# thinks.net
KiCad netlist of a schematic drawn in EAGLE
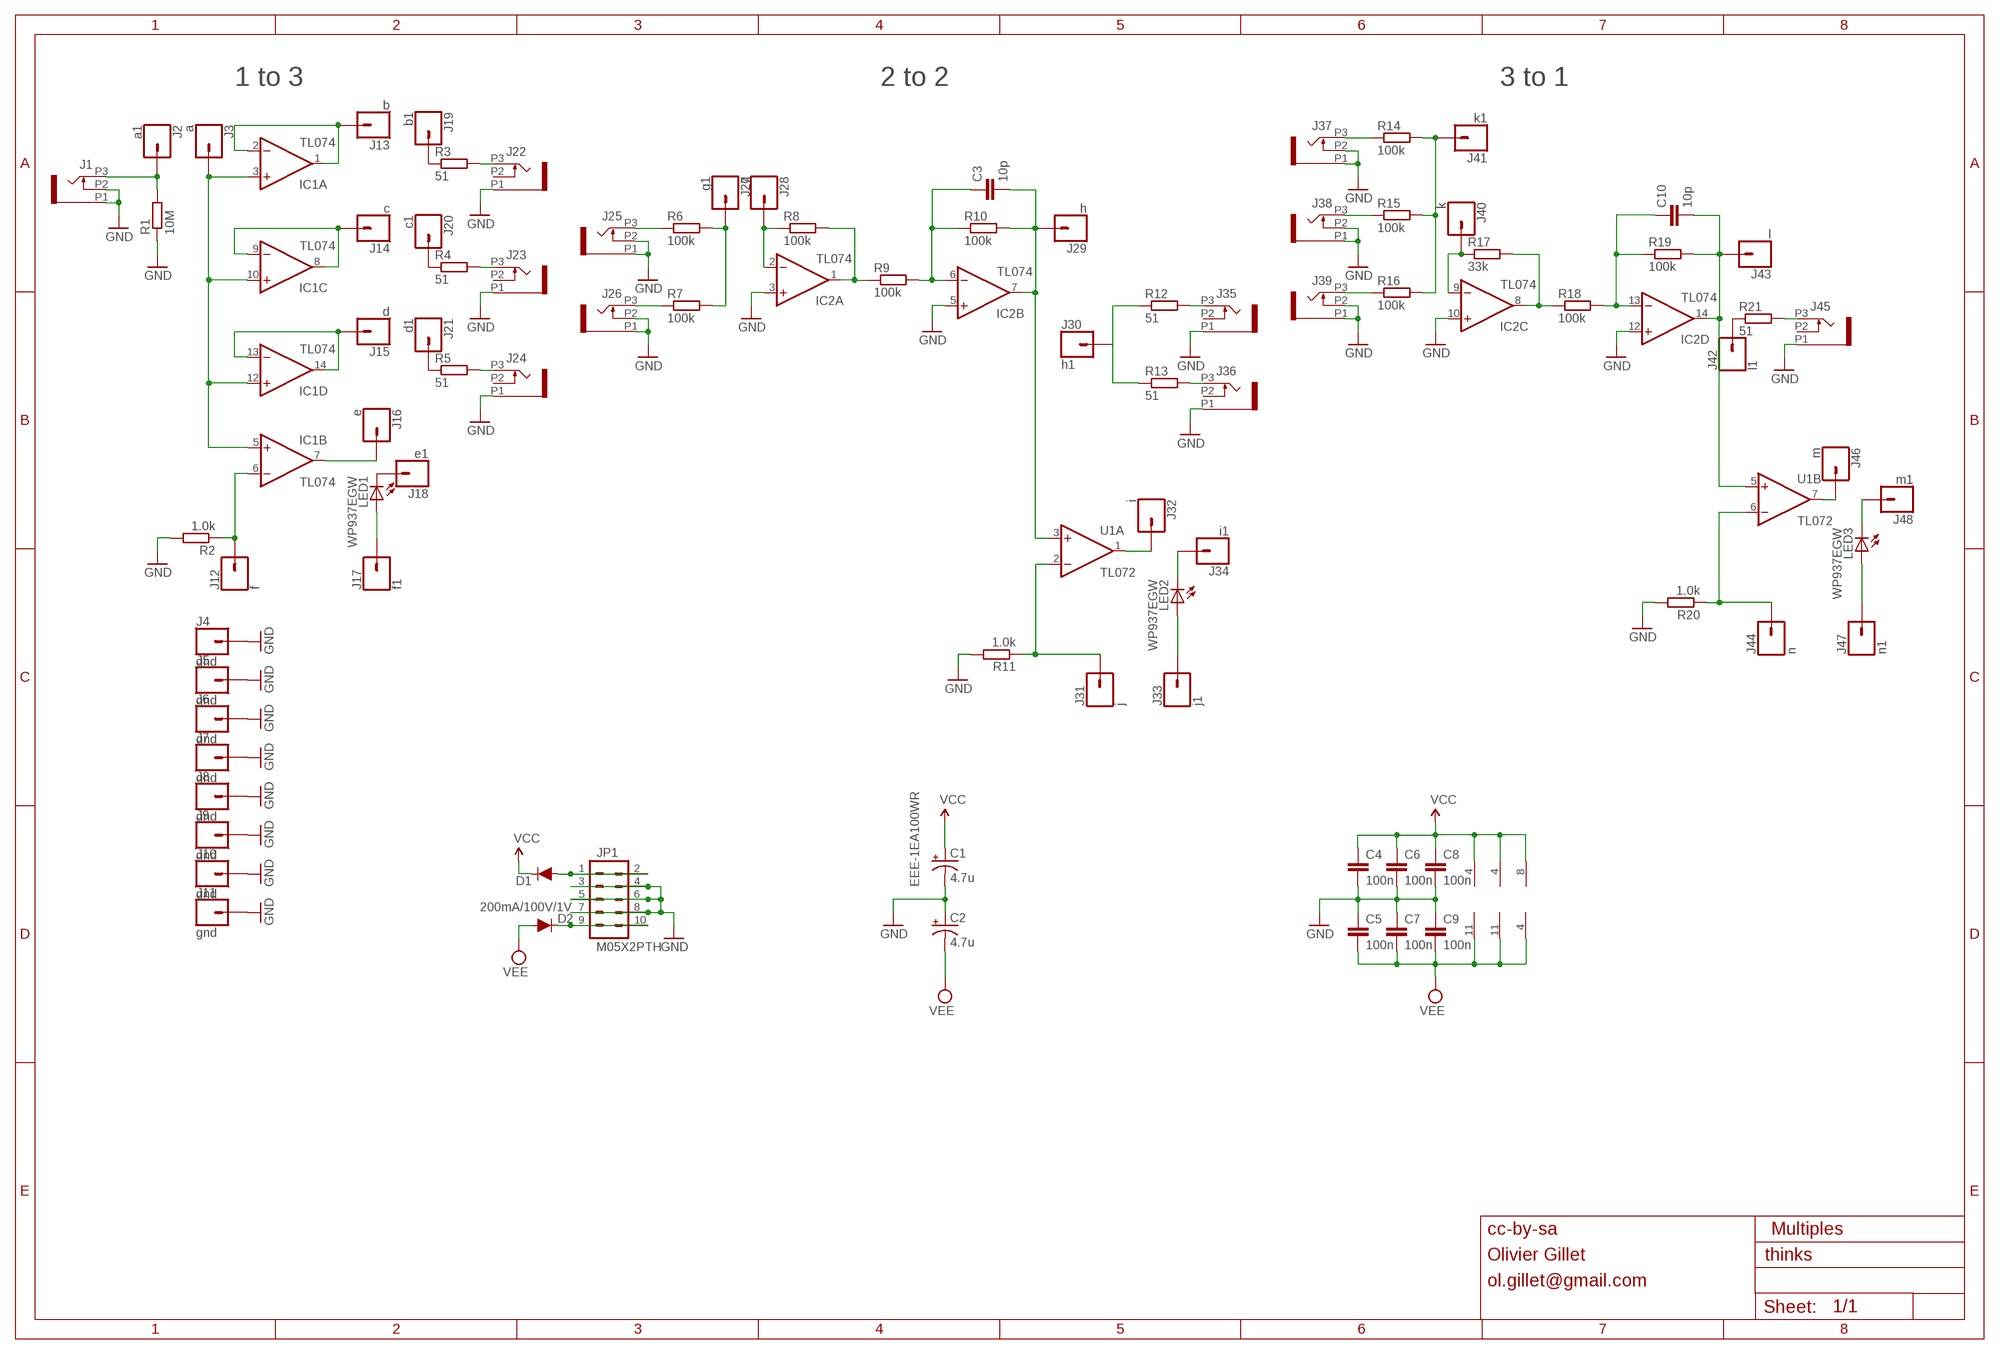
[diagram p0: schematic, sheet 1]

(export (version "E")
  (design (tool "Eeschema 10.0.6"))
  (components
    (comp (ref "C1")
      (value "4.7u")
      (footprint "eagle-import:E2,5-6")
      (libsource (lib "eagle-import") (part "CPOL-USE2.5-6"))
    )
    (comp (ref "C2")
      (value "4.7u")
      (footprint "eagle-import:E2,5-6")
      (libsource (lib "eagle-import") (part "CPOL-USE2.5-6"))
    )
    (comp (ref "C3")
      (value "10p")
      (footprint "eagle-import:C5B2.5")
      (libsource (lib "eagle-import") (part "C5/2.5"))
    )
    (comp (ref "C4")
      (value "100n")
      (footprint "eagle-import:C5B2.5")
      (libsource (lib "eagle-import") (part "C5/2.5"))
    )
    (comp (ref "C5")
      (value "100n")
      (footprint "eagle-import:C5B2.5")
      (libsource (lib "eagle-import") (part "C5/2.5"))
    )
    (comp (ref "C6")
      (value "100n")
      (footprint "eagle-import:C5B2.5")
      (libsource (lib "eagle-import") (part "C5/2.5"))
    )
    (comp (ref "C7")
      (value "100n")
      (footprint "eagle-import:C5B2.5")
      (libsource (lib "eagle-import") (part "C5/2.5"))
    )
    (comp (ref "C8")
      (value "100n")
      (footprint "eagle-import:C5B2.5")
      (libsource (lib "eagle-import") (part "C5/2.5"))
    )
    (comp (ref "C9")
      (value "100n")
      (footprint "eagle-import:C5B2.5")
      (libsource (lib "eagle-import") (part "C5/2.5"))
    )
    (comp (ref "C10")
      (value "10p")
      (footprint "eagle-import:C5B2.5")
      (libsource (lib "eagle-import") (part "C5/2.5"))
    )
    (comp (ref "D1")
      (value "200mA/100V/1V")
      (footprint "eagle-import:DIODE-1N4148")
      (libsource (lib "eagle-import") (part "DIODE-1N4148"))
    )
    (comp (ref "D2")
      (value "200mA/100V/1V")
      (footprint "eagle-import:DIODE-1N4148")
      (libsource (lib "eagle-import") (part "DIODE-1N4148"))
    )
    (comp (ref "IC1")
      (value "TL074")
      (footprint "eagle-import:DIL14")
      (libsource (lib "eagle-import") (part "TL074P"))
    )
    (comp (ref "IC2")
      (value "TL074")
      (footprint "eagle-import:DIL14")
      (libsource (lib "eagle-import") (part "TL074P"))
    )
    (comp (ref "J1")
      (value "PJ301_THONKICONN6")
      (footprint "eagle-import:WQP_PJ_301M6")
      (libsource (lib "eagle-import") (part "PJ301_THONKICONN6"))
    )
    (comp (ref "J2")
      (value "a1")
      (footprint "eagle-import:1X01")
      (libsource (lib "eagle-import") (part "CONN_01"))
    )
    (comp (ref "J3")
      (value "a")
      (footprint "eagle-import:1X01")
      (libsource (lib "eagle-import") (part "CONN_01"))
    )
    (comp (ref "J4")
      (value "gnd")
      (footprint "eagle-import:1X01")
      (libsource (lib "eagle-import") (part "CONN_01"))
    )
    (comp (ref "J5")
      (value "gnd")
      (footprint "eagle-import:1X01")
      (libsource (lib "eagle-import") (part "CONN_01"))
    )
    (comp (ref "J6")
      (value "gnd")
      (footprint "eagle-import:1X01")
      (libsource (lib "eagle-import") (part "CONN_01"))
    )
    (comp (ref "J7")
      (value "gnd")
      (footprint "eagle-import:1X01")
      (libsource (lib "eagle-import") (part "CONN_01"))
    )
    (comp (ref "J8")
      (value "gnd")
      (footprint "eagle-import:1X01")
      (libsource (lib "eagle-import") (part "CONN_01"))
    )
    (comp (ref "J9")
      (value "gnd")
      (footprint "eagle-import:1X01")
      (libsource (lib "eagle-import") (part "CONN_01"))
    )
    (comp (ref "J10")
      (value "gnd")
      (footprint "eagle-import:1X01")
      (libsource (lib "eagle-import") (part "CONN_01"))
    )
    (comp (ref "J11")
      (value "gnd")
      (footprint "eagle-import:1X01")
      (libsource (lib "eagle-import") (part "CONN_01"))
    )
    (comp (ref "J12")
      (value "f")
      (footprint "eagle-import:1X01")
      (libsource (lib "eagle-import") (part "CONN_01"))
    )
    (comp (ref "J13")
      (value "b")
      (footprint "eagle-import:1X01")
      (libsource (lib "eagle-import") (part "CONN_01"))
    )
    (comp (ref "J14")
      (value "c")
      (footprint "eagle-import:1X01")
      (libsource (lib "eagle-import") (part "CONN_01"))
    )
    (comp (ref "J15")
      (value "d")
      (footprint "eagle-import:1X01")
      (libsource (lib "eagle-import") (part "CONN_01"))
    )
    (comp (ref "J16")
      (value "e")
      (footprint "eagle-import:1X01")
      (libsource (lib "eagle-import") (part "CONN_01"))
    )
    (comp (ref "J17")
      (value "f1")
      (footprint "eagle-import:1X01")
      (libsource (lib "eagle-import") (part "CONN_01"))
    )
    (comp (ref "J18")
      (value "e1")
      (footprint "eagle-import:1X01")
      (libsource (lib "eagle-import") (part "CONN_01"))
    )
    (comp (ref "J19")
      (value "b1")
      (footprint "eagle-import:1X01")
      (libsource (lib "eagle-import") (part "CONN_01"))
    )
    (comp (ref "J20")
      (value "c1")
      (footprint "eagle-import:1X01")
      (libsource (lib "eagle-import") (part "CONN_01"))
    )
    (comp (ref "J21")
      (value "d1")
      (footprint "eagle-import:1X01")
      (libsource (lib "eagle-import") (part "CONN_01"))
    )
    (comp (ref "J22")
      (value "PJ301_THONKICONN6")
      (footprint "eagle-import:WQP_PJ_301M6")
      (libsource (lib "eagle-import") (part "PJ301_THONKICONN6"))
    )
    (comp (ref "J23")
      (value "PJ301_THONKICONN6")
      (footprint "eagle-import:WQP_PJ_301M6")
      (libsource (lib "eagle-import") (part "PJ301_THONKICONN6"))
    )
    (comp (ref "J24")
      (value "PJ301_THONKICONN6")
      (footprint "eagle-import:WQP_PJ_301M6")
      (libsource (lib "eagle-import") (part "PJ301_THONKICONN6"))
    )
    (comp (ref "J25")
      (value "PJ301_THONKICONN6")
      (footprint "eagle-import:WQP_PJ_301M6")
      (libsource (lib "eagle-import") (part "PJ301_THONKICONN6"))
    )
    (comp (ref "J26")
      (value "PJ301_THONKICONN6")
      (footprint "eagle-import:WQP_PJ_301M6")
      (libsource (lib "eagle-import") (part "PJ301_THONKICONN6"))
    )
    (comp (ref "J27")
      (value "g1")
      (footprint "eagle-import:1X01")
      (libsource (lib "eagle-import") (part "CONN_01"))
    )
    (comp (ref "J28")
      (value "g")
      (footprint "eagle-import:1X01")
      (libsource (lib "eagle-import") (part "CONN_01"))
    )
    (comp (ref "J29")
      (value "h")
      (footprint "eagle-import:1X01")
      (libsource (lib "eagle-import") (part "CONN_01"))
    )
    (comp (ref "J30")
      (value "h1")
      (footprint "eagle-import:1X01")
      (libsource (lib "eagle-import") (part "CONN_01"))
    )
    (comp (ref "J31")
      (value "j")
      (footprint "eagle-import:1X01")
      (libsource (lib "eagle-import") (part "CONN_01"))
    )
    (comp (ref "J32")
      (value "i")
      (footprint "eagle-import:1X01")
      (libsource (lib "eagle-import") (part "CONN_01"))
    )
    (comp (ref "J33")
      (value "j1")
      (footprint "eagle-import:1X01")
      (libsource (lib "eagle-import") (part "CONN_01"))
    )
    (comp (ref "J34")
      (value "i1")
      (footprint "eagle-import:1X01")
      (libsource (lib "eagle-import") (part "CONN_01"))
    )
    (comp (ref "J35")
      (value "PJ301_THONKICONN6")
      (footprint "eagle-import:WQP_PJ_301M6")
      (libsource (lib "eagle-import") (part "PJ301_THONKICONN6"))
    )
    (comp (ref "J36")
      (value "PJ301_THONKICONN6")
      (footprint "eagle-import:WQP_PJ_301M6")
      (libsource (lib "eagle-import") (part "PJ301_THONKICONN6"))
    )
    (comp (ref "J37")
      (value "PJ301_THONKICONN6")
      (footprint "eagle-import:WQP_PJ_301M6")
      (libsource (lib "eagle-import") (part "PJ301_THONKICONN6"))
    )
    (comp (ref "J38")
      (value "PJ301_THONKICONN6")
      (footprint "eagle-import:WQP_PJ_301M6")
      (libsource (lib "eagle-import") (part "PJ301_THONKICONN6"))
    )
    (comp (ref "J39")
      (value "PJ301_THONKICONN6")
      (footprint "eagle-import:WQP_PJ_301M6")
      (libsource (lib "eagle-import") (part "PJ301_THONKICONN6"))
    )
    (comp (ref "J40")
      (value "k")
      (footprint "eagle-import:1X01")
      (libsource (lib "eagle-import") (part "CONN_01"))
    )
    (comp (ref "J41")
      (value "k1")
      (footprint "eagle-import:1X01")
      (libsource (lib "eagle-import") (part "CONN_01"))
    )
    (comp (ref "J42")
      (value "l1")
      (footprint "eagle-import:1X01")
      (libsource (lib "eagle-import") (part "CONN_01"))
    )
    (comp (ref "J43")
      (value "l")
      (footprint "eagle-import:1X01")
      (libsource (lib "eagle-import") (part "CONN_01"))
    )
    (comp (ref "J44")
      (value "n")
      (footprint "eagle-import:1X01")
      (libsource (lib "eagle-import") (part "CONN_01"))
    )
    (comp (ref "J45")
      (value "PJ301_THONKICONN6")
      (footprint "eagle-import:WQP_PJ_301M6")
      (libsource (lib "eagle-import") (part "PJ301_THONKICONN6"))
    )
    (comp (ref "J46")
      (value "m")
      (footprint "eagle-import:1X01")
      (libsource (lib "eagle-import") (part "CONN_01"))
    )
    (comp (ref "J47")
      (value "n1")
      (footprint "eagle-import:1X01")
      (libsource (lib "eagle-import") (part "CONN_01"))
    )
    (comp (ref "J48")
      (value "m1")
      (footprint "eagle-import:1X01")
      (libsource (lib "eagle-import") (part "CONN_01"))
    )
    (comp (ref "JP1")
      (value "M05X2PTH")
      (footprint "eagle-import:AVR_ICSP")
      (libsource (lib "eagle-import") (part "M05X2PTH"))
    )
    (comp (ref "LED1")
      (value "WP937EGW")
      (footprint "eagle-import:LED3MM")
      (libsource (lib "eagle-import") (part "LED3MM"))
    )
    (comp (ref "LED2")
      (value "WP937EGW")
      (footprint "eagle-import:LED3MM")
      (libsource (lib "eagle-import") (part "LED3MM"))
    )
    (comp (ref "LED3")
      (value "WP937EGW")
      (footprint "eagle-import:LED3MM")
      (libsource (lib "eagle-import") (part "LED3MM"))
    )
    (comp (ref "R1")
      (value "10M")
      (footprint "eagle-import:VERTICAL_RESISTOR")
      (libsource (lib "eagle-import") (part "RESISTORVERTICAL"))
    )
    (comp (ref "R2")
      (value "1.0k")
      (footprint "eagle-import:VERTICAL_RESISTOR")
      (libsource (lib "eagle-import") (part "RESISTORVERTICAL"))
    )
    (comp (ref "R3")
      (value "51")
      (footprint "eagle-import:VERTICAL_RESISTOR")
      (libsource (lib "eagle-import") (part "RESISTORVERTICAL"))
    )
    (comp (ref "R4")
      (value "51")
      (footprint "eagle-import:VERTICAL_RESISTOR")
      (libsource (lib "eagle-import") (part "RESISTORVERTICAL"))
    )
    (comp (ref "R5")
      (value "51")
      (footprint "eagle-import:VERTICAL_RESISTOR")
      (libsource (lib "eagle-import") (part "RESISTORVERTICAL"))
    )
    (comp (ref "R6")
      (value "100k")
      (footprint "eagle-import:VERTICAL_RESISTOR")
      (libsource (lib "eagle-import") (part "RESISTORVERTICAL"))
    )
    (comp (ref "R7")
      (value "100k")
      (footprint "eagle-import:VERTICAL_RESISTOR")
      (libsource (lib "eagle-import") (part "RESISTORVERTICAL"))
    )
    (comp (ref "R8")
      (value "100k")
      (footprint "eagle-import:VERTICAL_RESISTOR")
      (libsource (lib "eagle-import") (part "RESISTORVERTICAL"))
    )
    (comp (ref "R9")
      (value "100k")
      (footprint "eagle-import:VERTICAL_RESISTOR")
      (libsource (lib "eagle-import") (part "RESISTORVERTICAL"))
    )
    (comp (ref "R10")
      (value "100k")
      (footprint "eagle-import:VERTICAL_RESISTOR")
      (libsource (lib "eagle-import") (part "RESISTORVERTICAL"))
    )
    (comp (ref "R11")
      (value "1.0k")
      (footprint "eagle-import:VERTICAL_RESISTOR")
      (libsource (lib "eagle-import") (part "RESISTORVERTICAL"))
    )
    (comp (ref "R12")
      (value "51")
      (footprint "eagle-import:VERTICAL_RESISTOR")
      (libsource (lib "eagle-import") (part "RESISTORVERTICAL"))
    )
    (comp (ref "R13")
      (value "51")
      (footprint "eagle-import:VERTICAL_RESISTOR")
      (libsource (lib "eagle-import") (part "RESISTORVERTICAL"))
    )
    (comp (ref "R14")
      (value "100k")
      (footprint "eagle-import:VERTICAL_RESISTOR")
      (libsource (lib "eagle-import") (part "RESISTORVERTICAL"))
    )
    (comp (ref "R15")
      (value "100k")
      (footprint "eagle-import:VERTICAL_RESISTOR")
      (libsource (lib "eagle-import") (part "RESISTORVERTICAL"))
    )
    (comp (ref "R16")
      (value "100k")
      (footprint "eagle-import:VERTICAL_RESISTOR")
      (libsource (lib "eagle-import") (part "RESISTORVERTICAL"))
    )
    (comp (ref "R17")
      (value "33k")
      (footprint "eagle-import:VERTICAL_RESISTOR")
      (libsource (lib "eagle-import") (part "RESISTORVERTICAL"))
    )
    (comp (ref "R18")
      (value "100k")
      (footprint "eagle-import:VERTICAL_RESISTOR")
      (libsource (lib "eagle-import") (part "RESISTORVERTICAL"))
    )
    (comp (ref "R19")
      (value "100k")
      (footprint "eagle-import:VERTICAL_RESISTOR")
      (libsource (lib "eagle-import") (part "RESISTORVERTICAL"))
    )
    (comp (ref "R20")
      (value "1.0k")
      (footprint "eagle-import:VERTICAL_RESISTOR")
      (libsource (lib "eagle-import") (part "RESISTORVERTICAL"))
    )
    (comp (ref "R21")
      (value "51")
      (footprint "eagle-import:VERTICAL_RESISTOR")
      (libsource (lib "eagle-import") (part "RESISTORVERTICAL"))
    )
    (comp (ref "U1")
      (value "TL072")
      (footprint "eagle-import:DIL08")
      (libsource (lib "eagle-import") (part "OP_DUAL_"))
    )
  )
  (nets
    (net (code "1") (name "GND") (class "Default")
      (node (ref "C1") (pin "-") (pinfunction "-_-") (pintype "passive"))
      (node (ref "C2") (pin "+") (pinfunction "+_+") (pintype "passive"))
      (node (ref "C4") (pin "2") (pinfunction "2_2") (pintype "passive"))
      (node (ref "C5") (pin "1") (pinfunction "1_1") (pintype "passive"))
      (node (ref "C6") (pin "2") (pinfunction "2_2") (pintype "passive"))
      (node (ref "C7") (pin "1") (pinfunction "1_1") (pintype "passive"))
      (node (ref "C8") (pin "2") (pinfunction "2_2") (pintype "passive"))
      (node (ref "C9") (pin "1") (pinfunction "1_1") (pintype "passive"))
      (node (ref "IC2") (pin "10") (pinfunction "+IN_10") (pintype "input"))
      (node (ref "IC2") (pin "12") (pinfunction "+IN_12") (pintype "input"))
      (node (ref "IC2") (pin "3") (pinfunction "+IN_3") (pintype "input"))
      (node (ref "IC2") (pin "5") (pinfunction "+IN_5") (pintype "input"))
      (node (ref "J1") (pin "P1") (pinfunction "1_P1") (pintype "passive"))
      (node (ref "J1") (pin "P2") (pinfunction "2_P2") (pintype "passive"))
      (node (ref "J10") (pin "1") (pinfunction "1_1") (pintype "passive"))
      (node (ref "J11") (pin "1") (pinfunction "1_1") (pintype "passive"))
      (node (ref "J22") (pin "P1") (pinfunction "1_P1") (pintype "passive"))
      (node (ref "J23") (pin "P1") (pinfunction "1_P1") (pintype "passive"))
      (node (ref "J24") (pin "P1") (pinfunction "1_P1") (pintype "passive"))
      (node (ref "J25") (pin "P1") (pinfunction "1_P1") (pintype "passive"))
      (node (ref "J25") (pin "P2") (pinfunction "2_P2") (pintype "passive"))
      (node (ref "J26") (pin "P1") (pinfunction "1_P1") (pintype "passive"))
      (node (ref "J26") (pin "P2") (pinfunction "2_P2") (pintype "passive"))
      (node (ref "J35") (pin "P1") (pinfunction "1_P1") (pintype "passive"))
      (node (ref "J36") (pin "P1") (pinfunction "1_P1") (pintype "passive"))
      (node (ref "J37") (pin "P1") (pinfunction "1_P1") (pintype "passive"))
      (node (ref "J37") (pin "P2") (pinfunction "2_P2") (pintype "passive"))
      (node (ref "J38") (pin "P1") (pinfunction "1_P1") (pintype "passive"))
      (node (ref "J38") (pin "P2") (pinfunction "2_P2") (pintype "passive"))
      (node (ref "J39") (pin "P1") (pinfunction "1_P1") (pintype "passive"))
      (node (ref "J39") (pin "P2") (pinfunction "2_P2") (pintype "passive"))
      (node (ref "J4") (pin "1") (pinfunction "1_1") (pintype "passive"))
      (node (ref "J45") (pin "P1") (pinfunction "1_P1") (pintype "passive"))
      (node (ref "J5") (pin "1") (pinfunction "1_1") (pintype "passive"))
      (node (ref "J6") (pin "1") (pinfunction "1_1") (pintype "passive"))
      (node (ref "J7") (pin "1") (pinfunction "1_1") (pintype "passive"))
      (node (ref "J8") (pin "1") (pinfunction "1_1") (pintype "passive"))
      (node (ref "J9") (pin "1") (pinfunction "1_1") (pintype "passive"))
      (node (ref "JP1") (pin "3") (pinfunction "3_3") (pintype "passive"))
      (node (ref "JP1") (pin "4") (pinfunction "4_4") (pintype "passive"))
      (node (ref "JP1") (pin "5") (pinfunction "5_5") (pintype "passive"))
      (node (ref "JP1") (pin "6") (pinfunction "6_6") (pintype "passive"))
      (node (ref "JP1") (pin "7") (pinfunction "7_7") (pintype "passive"))
      (node (ref "JP1") (pin "8") (pinfunction "8_8") (pintype "passive"))
      (node (ref "R1") (pin "1") (pinfunction "1_1") (pintype "passive"))
      (node (ref "R11") (pin "2") (pinfunction "2_2") (pintype "passive"))
      (node (ref "R2") (pin "2") (pinfunction "2_2") (pintype "passive"))
      (node (ref "R20") (pin "2") (pinfunction "2_2") (pintype "passive"))
    )
    (net (code "2") (name "Net-(D1-PadA)") (class "Default")
      (node (ref "D1") (pin "A") (pinfunction "A_A") (pintype "passive"))
      (node (ref "JP1") (pin "1") (pinfunction "1_1") (pintype "passive"))
      (node (ref "JP1") (pin "2") (pinfunction "2_2") (pintype "passive"))
    )
    (net (code "3") (name "Net-(D2-PadC)") (class "Default")
      (node (ref "D2") (pin "C") (pinfunction "C_C") (pintype "passive"))
      (node (ref "JP1") (pin "10") (pinfunction "10_10") (pintype "passive"))
      (node (ref "JP1") (pin "9") (pinfunction "9_9") (pintype "passive"))
    )
    (net (code "4") (name "Net-(IC1A-+IN)") (class "Default")
      (node (ref "IC1") (pin "10") (pinfunction "+IN_10") (pintype "input"))
      (node (ref "IC1") (pin "12") (pinfunction "+IN_12") (pintype "input"))
      (node (ref "IC1") (pin "3") (pinfunction "+IN_3") (pintype "input"))
      (node (ref "IC1") (pin "5") (pinfunction "+IN_5") (pintype "input"))
      (node (ref "J3") (pin "1") (pinfunction "1_1") (pintype "passive"))
    )
    (net (code "5") (name "Net-(IC1A--IN)") (class "Default")
      (node (ref "IC1") (pin "1") (pinfunction "OUT_1") (pintype "output"))
      (node (ref "IC1") (pin "2") (pinfunction "-IN_2") (pintype "input"))
      (node (ref "J13") (pin "1") (pinfunction "1_1") (pintype "passive"))
    )
    (net (code "6") (name "Net-(IC1B--IN)") (class "Default")
      (node (ref "IC1") (pin "6") (pinfunction "-IN_6") (pintype "input"))
      (node (ref "J12") (pin "1") (pinfunction "1_1") (pintype "passive"))
      (node (ref "R2") (pin "1") (pinfunction "1_1") (pintype "passive"))
    )
    (net (code "7") (name "Net-(IC1B-OUT)") (class "Default")
      (node (ref "IC1") (pin "7") (pinfunction "OUT_7") (pintype "output"))
      (node (ref "J16") (pin "1") (pinfunction "1_1") (pintype "passive"))
    )
    (net (code "8") (name "Net-(IC1C--IN)") (class "Default")
      (node (ref "IC1") (pin "8") (pinfunction "OUT_8") (pintype "output"))
      (node (ref "IC1") (pin "9") (pinfunction "-IN_9") (pintype "input"))
      (node (ref "J14") (pin "1") (pinfunction "1_1") (pintype "passive"))
    )
    (net (code "9") (name "Net-(IC1D--IN)") (class "Default")
      (node (ref "IC1") (pin "13") (pinfunction "-IN_13") (pintype "input"))
      (node (ref "IC1") (pin "14") (pinfunction "OUT_14") (pintype "output"))
      (node (ref "J15") (pin "1") (pinfunction "1_1") (pintype "passive"))
    )
    (net (code "10") (name "Net-(IC2A--IN)") (class "Default")
      (node (ref "IC2") (pin "2") (pinfunction "-IN_2") (pintype "input"))
      (node (ref "J28") (pin "1") (pinfunction "1_1") (pintype "passive"))
      (node (ref "R8") (pin "1") (pinfunction "1_1") (pintype "passive"))
    )
    (net (code "11") (name "Net-(IC2A-OUT)") (class "Default")
      (node (ref "IC2") (pin "1") (pinfunction "OUT_1") (pintype "output"))
      (node (ref "R8") (pin "2") (pinfunction "2_2") (pintype "passive"))
      (node (ref "R9") (pin "1") (pinfunction "1_1") (pintype "passive"))
    )
    (net (code "12") (name "Net-(IC2B--IN)") (class "Default")
      (node (ref "C3") (pin "1") (pinfunction "1_1") (pintype "passive"))
      (node (ref "IC2") (pin "6") (pinfunction "-IN_6") (pintype "input"))
      (node (ref "R10") (pin "1") (pinfunction "1_1") (pintype "passive"))
      (node (ref "R9") (pin "2") (pinfunction "2_2") (pintype "passive"))
    )
    (net (code "13") (name "Net-(IC2B-OUT)") (class "Default")
      (node (ref "C3") (pin "2") (pinfunction "2_2") (pintype "passive"))
      (node (ref "IC2") (pin "7") (pinfunction "OUT_7") (pintype "output"))
      (node (ref "J29") (pin "1") (pinfunction "1_1") (pintype "passive"))
      (node (ref "R10") (pin "2") (pinfunction "2_2") (pintype "passive"))
      (node (ref "U1") (pin "3") (pinfunction "+IN_3") (pintype "input"))
    )
    (net (code "14") (name "Net-(IC2C--IN)") (class "Default")
      (node (ref "IC2") (pin "9") (pinfunction "-IN_9") (pintype "input"))
      (node (ref "J40") (pin "1") (pinfunction "1_1") (pintype "passive"))
      (node (ref "R17") (pin "1") (pinfunction "1_1") (pintype "passive"))
    )
    (net (code "15") (name "Net-(IC2C-OUT)") (class "Default")
      (node (ref "IC2") (pin "8") (pinfunction "OUT_8") (pintype "output"))
      (node (ref "R17") (pin "2") (pinfunction "2_2") (pintype "passive"))
      (node (ref "R18") (pin "1") (pinfunction "1_1") (pintype "passive"))
    )
    (net (code "16") (name "Net-(IC2D--IN)") (class "Default")
      (node (ref "C10") (pin "1") (pinfunction "1_1") (pintype "passive"))
      (node (ref "IC2") (pin "13") (pinfunction "-IN_13") (pintype "input"))
      (node (ref "R18") (pin "2") (pinfunction "2_2") (pintype "passive"))
      (node (ref "R19") (pin "1") (pinfunction "1_1") (pintype "passive"))
    )
    (net (code "17") (name "Net-(IC2D-OUT)") (class "Default")
      (node (ref "C10") (pin "2") (pinfunction "2_2") (pintype "passive"))
      (node (ref "IC2") (pin "14") (pinfunction "OUT_14") (pintype "output"))
      (node (ref "J43") (pin "1") (pinfunction "1_1") (pintype "passive"))
      (node (ref "R19") (pin "2") (pinfunction "2_2") (pintype "passive"))
      (node (ref "U1") (pin "5") (pinfunction "+IN_5") (pintype "input"))
    )
    (net (code "18") (name "Net-(J1-3)") (class "Default")
      (node (ref "J1") (pin "P3") (pinfunction "3_P3") (pintype "passive"))
      (node (ref "J2") (pin "1") (pinfunction "1_1") (pintype "passive"))
      (node (ref "R1") (pin "2") (pinfunction "2_2") (pintype "passive"))
    )
    (net (code "19") (name "Net-(J17-Pad1)") (class "Default")
      (node (ref "J17") (pin "1") (pinfunction "1_1") (pintype "passive"))
      (node (ref "LED1") (pin "A") (pinfunction "A_A") (pintype "passive"))
    )
    (net (code "20") (name "Net-(J19-Pad1)") (class "Default")
      (node (ref "J19") (pin "1") (pinfunction "1_1") (pintype "passive"))
      (node (ref "R3") (pin "1") (pinfunction "1_1") (pintype "passive"))
    )
    (net (code "21") (name "Net-(J20-Pad1)") (class "Default")
      (node (ref "J20") (pin "1") (pinfunction "1_1") (pintype "passive"))
      (node (ref "R4") (pin "1") (pinfunction "1_1") (pintype "passive"))
    )
    (net (code "22") (name "Net-(J21-Pad1)") (class "Default")
      (node (ref "J21") (pin "1") (pinfunction "1_1") (pintype "passive"))
      (node (ref "R5") (pin "1") (pinfunction "1_1") (pintype "passive"))
    )
    (net (code "23") (name "Net-(J22-3)") (class "Default")
      (node (ref "J22") (pin "P3") (pinfunction "3_P3") (pintype "passive"))
      (node (ref "R3") (pin "2") (pinfunction "2_2") (pintype "passive"))
    )
    (net (code "24") (name "Net-(J23-3)") (class "Default")
      (node (ref "J23") (pin "P3") (pinfunction "3_P3") (pintype "passive"))
      (node (ref "R4") (pin "2") (pinfunction "2_2") (pintype "passive"))
    )
    (net (code "25") (name "Net-(J24-3)") (class "Default")
      (node (ref "J24") (pin "P3") (pinfunction "3_P3") (pintype "passive"))
      (node (ref "R5") (pin "2") (pinfunction "2_2") (pintype "passive"))
    )
    (net (code "26") (name "Net-(J25-3)") (class "Default")
      (node (ref "J25") (pin "P3") (pinfunction "3_P3") (pintype "passive"))
      (node (ref "R6") (pin "1") (pinfunction "1_1") (pintype "passive"))
    )
    (net (code "27") (name "Net-(J26-3)") (class "Default")
      (node (ref "J26") (pin "P3") (pinfunction "3_P3") (pintype "passive"))
      (node (ref "R7") (pin "1") (pinfunction "1_1") (pintype "passive"))
    )
    (net (code "28") (name "Net-(J27-Pad1)") (class "Default")
      (node (ref "J27") (pin "1") (pinfunction "1_1") (pintype "passive"))
      (node (ref "R6") (pin "2") (pinfunction "2_2") (pintype "passive"))
      (node (ref "R7") (pin "2") (pinfunction "2_2") (pintype "passive"))
    )
    (net (code "29") (name "Net-(J30-Pad1)") (class "Default")
      (node (ref "J30") (pin "1") (pinfunction "1_1") (pintype "passive"))
      (node (ref "R12") (pin "1") (pinfunction "1_1") (pintype "passive"))
      (node (ref "R13") (pin "1") (pinfunction "1_1") (pintype "passive"))
    )
    (net (code "30") (name "Net-(J33-Pad1)") (class "Default")
      (node (ref "J33") (pin "1") (pinfunction "1_1") (pintype "passive"))
      (node (ref "LED2") (pin "A") (pinfunction "A_A") (pintype "passive"))
    )
    (net (code "31") (name "Net-(J35-3)") (class "Default")
      (node (ref "J35") (pin "P3") (pinfunction "3_P3") (pintype "passive"))
      (node (ref "R12") (pin "2") (pinfunction "2_2") (pintype "passive"))
    )
    (net (code "32") (name "Net-(J36-3)") (class "Default")
      (node (ref "J36") (pin "P3") (pinfunction "3_P3") (pintype "passive"))
      (node (ref "R13") (pin "2") (pinfunction "2_2") (pintype "passive"))
    )
    (net (code "33") (name "Net-(J37-3)") (class "Default")
      (node (ref "J37") (pin "P3") (pinfunction "3_P3") (pintype "passive"))
      (node (ref "R14") (pin "1") (pinfunction "1_1") (pintype "passive"))
    )
    (net (code "34") (name "Net-(J38-3)") (class "Default")
      (node (ref "J38") (pin "P3") (pinfunction "3_P3") (pintype "passive"))
      (node (ref "R15") (pin "1") (pinfunction "1_1") (pintype "passive"))
    )
    (net (code "35") (name "Net-(J39-3)") (class "Default")
      (node (ref "J39") (pin "P3") (pinfunction "3_P3") (pintype "passive"))
      (node (ref "R16") (pin "1") (pinfunction "1_1") (pintype "passive"))
    )
    (net (code "36") (name "Net-(J41-Pad1)") (class "Default")
      (node (ref "J41") (pin "1") (pinfunction "1_1") (pintype "passive"))
      (node (ref "R14") (pin "2") (pinfunction "2_2") (pintype "passive"))
      (node (ref "R15") (pin "2") (pinfunction "2_2") (pintype "passive"))
      (node (ref "R16") (pin "2") (pinfunction "2_2") (pintype "passive"))
    )
    (net (code "37") (name "Net-(J42-Pad1)") (class "Default")
      (node (ref "J42") (pin "1") (pinfunction "1_1") (pintype "passive"))
      (node (ref "R21") (pin "1") (pinfunction "1_1") (pintype "passive"))
    )
    (net (code "38") (name "Net-(J45-3)") (class "Default")
      (node (ref "J45") (pin "P3") (pinfunction "3_P3") (pintype "passive"))
      (node (ref "R21") (pin "2") (pinfunction "2_2") (pintype "passive"))
    )
    (net (code "39") (name "Net-(J47-Pad1)") (class "Default")
      (node (ref "J47") (pin "1") (pinfunction "1_1") (pintype "passive"))
      (node (ref "LED3") (pin "A") (pinfunction "A_A") (pintype "passive"))
    )
    (net (code "40") (name "Net-(LED1-C)") (class "Default")
      (node (ref "J18") (pin "1") (pinfunction "1_1") (pintype "passive"))
      (node (ref "LED1") (pin "K") (pinfunction "C_K") (pintype "passive"))
    )
    (net (code "41") (name "Net-(LED2-C)") (class "Default")
      (node (ref "J34") (pin "1") (pinfunction "1_1") (pintype "passive"))
      (node (ref "LED2") (pin "K") (pinfunction "C_K") (pintype "passive"))
    )
    (net (code "42") (name "Net-(LED3-C)") (class "Default")
      (node (ref "J48") (pin "1") (pinfunction "1_1") (pintype "passive"))
      (node (ref "LED3") (pin "K") (pinfunction "C_K") (pintype "passive"))
    )
    (net (code "43") (name "Net-(U1A--IN)") (class "Default")
      (node (ref "J31") (pin "1") (pinfunction "1_1") (pintype "passive"))
      (node (ref "R11") (pin "1") (pinfunction "1_1") (pintype "passive"))
      (node (ref "U1") (pin "2") (pinfunction "-IN_2") (pintype "input"))
    )
    (net (code "44") (name "Net-(U1A-OUT)") (class "Default")
      (node (ref "J32") (pin "1") (pinfunction "1_1") (pintype "passive"))
      (node (ref "U1") (pin "1") (pinfunction "OUT_1") (pintype "output"))
    )
    (net (code "45") (name "Net-(U1B--IN)") (class "Default")
      (node (ref "J44") (pin "1") (pinfunction "1_1") (pintype "passive"))
      (node (ref "R20") (pin "1") (pinfunction "1_1") (pintype "passive"))
      (node (ref "U1") (pin "6") (pinfunction "-IN_6") (pintype "input"))
    )
    (net (code "46") (name "Net-(U1B-OUT)") (class "Default")
      (node (ref "J46") (pin "1") (pinfunction "1_1") (pintype "passive"))
      (node (ref "U1") (pin "7") (pinfunction "OUT_7") (pintype "output"))
    )
    (net (code "47") (name "VCC") (class "Default")
      (node (ref "C1") (pin "+") (pinfunction "+_+") (pintype "passive"))
      (node (ref "C4") (pin "1") (pinfunction "1_1") (pintype "passive"))
      (node (ref "C6") (pin "1") (pinfunction "1_1") (pintype "passive"))
      (node (ref "C8") (pin "1") (pinfunction "1_1") (pintype "passive"))
      (node (ref "D1") (pin "C") (pinfunction "C_C") (pintype "passive"))
      (node (ref "IC1") (pin "4") (pinfunction "V+_4") (pintype "power_in"))
      (node (ref "IC2") (pin "4") (pinfunction "V+_4") (pintype "power_in"))
      (node (ref "U1") (pin "8") (pinfunction "V+_8") (pintype "power_in"))
    )
    (net (code "48") (name "VEE") (class "Default")
      (node (ref "C2") (pin "-") (pinfunction "-_-") (pintype "passive"))
      (node (ref "C5") (pin "2") (pinfunction "2_2") (pintype "passive"))
      (node (ref "C7") (pin "2") (pinfunction "2_2") (pintype "passive"))
      (node (ref "C9") (pin "2") (pinfunction "2_2") (pintype "passive"))
      (node (ref "D2") (pin "A") (pinfunction "A_A") (pintype "passive"))
      (node (ref "IC1") (pin "11") (pinfunction "V-_11") (pintype "power_in"))
      (node (ref "IC2") (pin "11") (pinfunction "V-_11") (pintype "power_in"))
      (node (ref "U1") (pin "4") (pinfunction "V-_4") (pintype "power_in"))
    )
    (net (code "49") (name "unconnected-(J22-2-PadP2)") (class "Default")
      (node (ref "J22") (pin "P2") (pinfunction "2_P2") (pintype "passive"))
    )
    (net (code "50") (name "unconnected-(J23-2-PadP2)") (class "Default")
      (node (ref "J23") (pin "P2") (pinfunction "2_P2") (pintype "passive"))
    )
    (net (code "51") (name "unconnected-(J24-2-PadP2)") (class "Default")
      (node (ref "J24") (pin "P2") (pinfunction "2_P2") (pintype "passive"))
    )
    (net (code "52") (name "unconnected-(J35-2-PadP2)") (class "Default")
      (node (ref "J35") (pin "P2") (pinfunction "2_P2") (pintype "passive"))
    )
    (net (code "53") (name "unconnected-(J36-2-PadP2)") (class "Default")
      (node (ref "J36") (pin "P2") (pinfunction "2_P2") (pintype "passive"))
    )
    (net (code "54") (name "unconnected-(J45-2-PadP2)") (class "Default")
      (node (ref "J45") (pin "P2") (pinfunction "2_P2") (pintype "passive"))
    )
  )
)
